# Lightpack_6_0_man.net
KiCad netlist of a schematic drawn in EAGLE
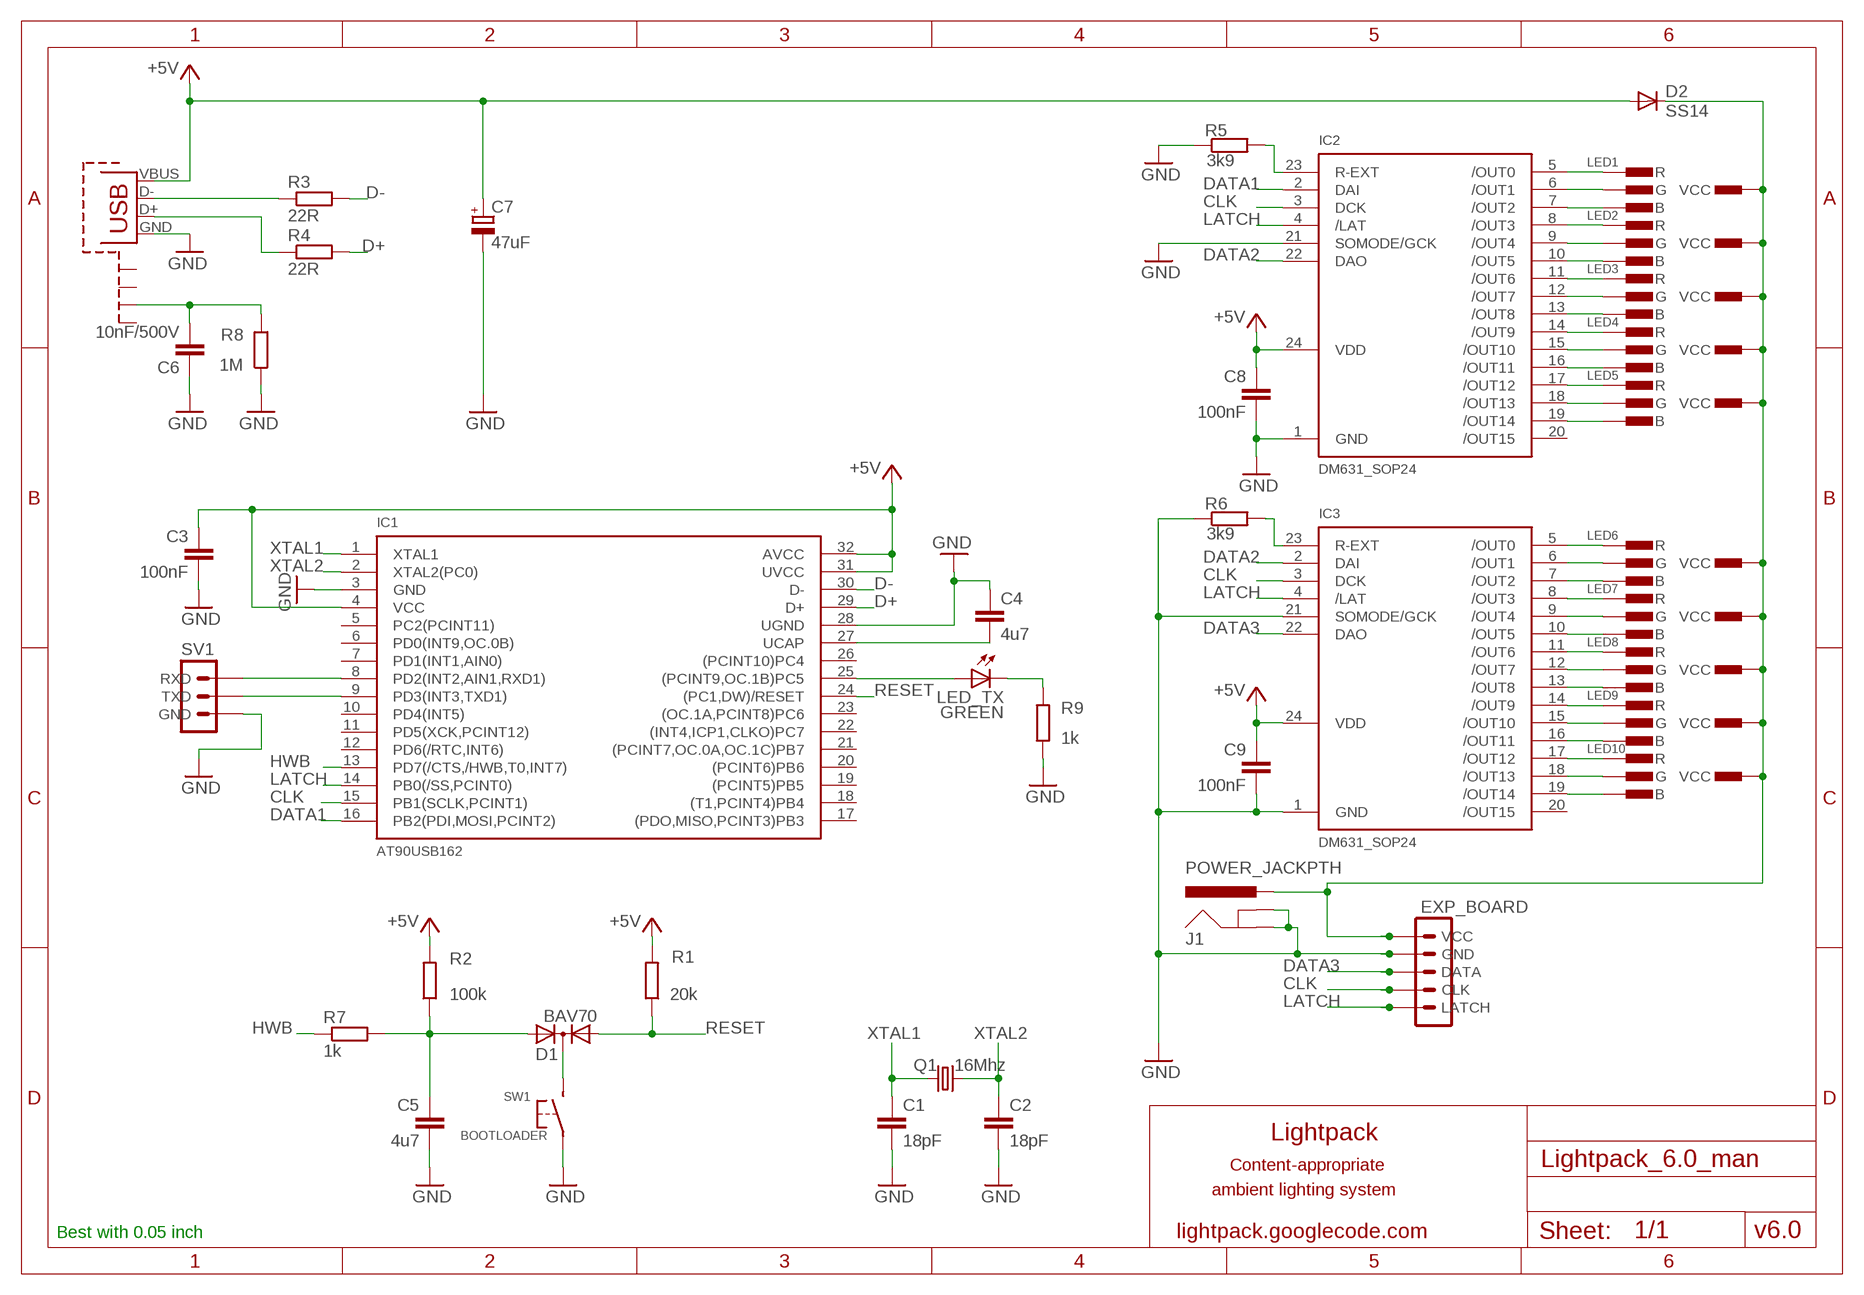
[diagram p0: schematic, sheet 1]

(export (version "E")
  (design (tool "Eeschema 10.0.6"))
  (components
    (comp (ref "C1")
      (value "18pF")
      (footprint "eagle-import:C0805")
      (libsource (lib "eagle-import") (part "C-EUC0805"))
    )
    (comp (ref "C2")
      (value "18pF")
      (footprint "eagle-import:C0805")
      (libsource (lib "eagle-import") (part "C-EUC0805"))
    )
    (comp (ref "C3")
      (value "100nF")
      (footprint "eagle-import:C0805")
      (libsource (lib "eagle-import") (part "C-EUC0805"))
    )
    (comp (ref "C4")
      (value "4u7")
      (footprint "eagle-import:C0805")
      (libsource (lib "eagle-import") (part "C-EUC0805"))
    )
    (comp (ref "C5")
      (value "4u7")
      (footprint "eagle-import:C0805")
      (libsource (lib "eagle-import") (part "C-EUC0805"))
    )
    (comp (ref "C6")
      (value "10nF/500V")
      (footprint "eagle-import:C0805")
      (libsource (lib "eagle-import") (part "C-EUC0805"))
    )
    (comp (ref "C7")
      (value "47uF")
      (footprint "eagle-import:SMC_D")
      (libsource (lib "eagle-import") (part "CPOL-EUSMCD"))
    )
    (comp (ref "C8")
      (value "100nF")
      (footprint "eagle-import:C0805")
      (libsource (lib "eagle-import") (part "C-EUC0805"))
    )
    (comp (ref "C9")
      (value "100nF")
      (footprint "eagle-import:C0805")
      (libsource (lib "eagle-import") (part "C-EUC0805"))
    )
    (comp (ref "D1")
      (value "BAV70")
      (footprint "eagle-import:SOT23")
      (libsource (lib "eagle-import") (part "DIODE-2AC|CASOT23"))
    )
    (comp (ref "D2")
      (value "SS14")
      (footprint "eagle-import:SMB")
      (libsource (lib "eagle-import") (part "DIODE-SMB"))
    )
    (comp (ref "EXP_BOARD")
      (value "MA05-1")
      (footprint "eagle-import:MA05-1")
      (libsource (lib "eagle-import") (part "MA05-1"))
    )
    (comp (ref "IC1")
      (value "AT90USB162")
      (footprint "eagle-import:TQFP32")
      (libsource (lib "eagle-import") (part "AT90USB162"))
    )
    (comp (ref "IC2")
      (value "DM631_SOP24")
      (footprint "eagle-import:SOP24-300-1.27")
      (libsource (lib "eagle-import") (part "DM631_SOP24"))
    )
    (comp (ref "IC3")
      (value "DM631_SOP24")
      (footprint "eagle-import:SOP24-300-1.27")
      (libsource (lib "eagle-import") (part "DM631_SOP24"))
    )
    (comp (ref "J1")
      (value "POWER_JACKPTH")
      (footprint "eagle-import:POWER_JACK_PTH")
      (libsource (lib "eagle-import") (part "POWER_JACKPTH"))
    )
    (comp (ref "LED1")
      (value "CON-RGB-LED")
      (footprint "eagle-import:CON-RGB-LED-TH")
      (libsource (lib "eagle-import") (part "CON-RGB-LED-TH"))
    )
    (comp (ref "LED2")
      (value "CON-RGB-LED")
      (footprint "eagle-import:CON-RGB-LED-TH")
      (libsource (lib "eagle-import") (part "CON-RGB-LED-TH"))
    )
    (comp (ref "LED3")
      (value "CON-RGB-LED")
      (footprint "eagle-import:CON-RGB-LED-TH")
      (libsource (lib "eagle-import") (part "CON-RGB-LED-TH"))
    )
    (comp (ref "LED4")
      (value "CON-RGB-LED")
      (footprint "eagle-import:CON-RGB-LED-TH")
      (libsource (lib "eagle-import") (part "CON-RGB-LED-TH"))
    )
    (comp (ref "LED5")
      (value "CON-RGB-LED")
      (footprint "eagle-import:CON-RGB-LED-TH")
      (libsource (lib "eagle-import") (part "CON-RGB-LED-TH"))
    )
    (comp (ref "LED6")
      (value "CON-RGB-LED")
      (footprint "eagle-import:CON-RGB-LED-TH")
      (libsource (lib "eagle-import") (part "CON-RGB-LED-TH"))
    )
    (comp (ref "LED7")
      (value "CON-RGB-LED")
      (footprint "eagle-import:CON-RGB-LED-TH")
      (libsource (lib "eagle-import") (part "CON-RGB-LED-TH"))
    )
    (comp (ref "LED8")
      (value "CON-RGB-LED")
      (footprint "eagle-import:CON-RGB-LED-TH")
      (libsource (lib "eagle-import") (part "CON-RGB-LED-TH"))
    )
    (comp (ref "LED9")
      (value "CON-RGB-LED")
      (footprint "eagle-import:CON-RGB-LED-TH")
      (libsource (lib "eagle-import") (part "CON-RGB-LED-TH"))
    )
    (comp (ref "LED10")
      (value "CON-RGB-LED")
      (footprint "eagle-import:CON-RGB-LED-TH")
      (libsource (lib "eagle-import") (part "CON-RGB-LED-TH"))
    )
    (comp (ref "LED_TX")
      (value "GREEN")
      (footprint "eagle-import:CHIPLED_0805")
      (libsource (lib "eagle-import") (part "LEDCHIPLED_0805"))
    )
    (comp (ref "Q1")
      (value "16Mhz")
      (footprint "eagle-import:HC49UP")
      (libsource (lib "eagle-import") (part "CRYSTALHC49UP"))
    )
    (comp (ref "R1")
      (value "20k")
      (footprint "eagle-import:R0805")
      (libsource (lib "eagle-import") (part "R-EU_R0805"))
    )
    (comp (ref "R2")
      (value "100k")
      (footprint "eagle-import:R0805")
      (libsource (lib "eagle-import") (part "R-EU_R0805"))
    )
    (comp (ref "R3")
      (value "22R")
      (footprint "eagle-import:R0805")
      (libsource (lib "eagle-import") (part "R-EU_R0805"))
    )
    (comp (ref "R4")
      (value "22R")
      (footprint "eagle-import:R0805")
      (libsource (lib "eagle-import") (part "R-EU_R0805"))
    )
    (comp (ref "R5")
      (value "3k9")
      (footprint "eagle-import:R0805")
      (libsource (lib "eagle-import") (part "R-EU_R0805"))
    )
    (comp (ref "R6")
      (value "3k9")
      (footprint "eagle-import:R0805")
      (libsource (lib "eagle-import") (part "R-EU_R0805"))
    )
    (comp (ref "R7")
      (value "1k")
      (footprint "eagle-import:R0805")
      (libsource (lib "eagle-import") (part "R-EU_R0805"))
    )
    (comp (ref "R8")
      (value "1M")
      (footprint "eagle-import:R0805")
      (libsource (lib "eagle-import") (part "R-EU_R0805"))
    )
    (comp (ref "R9")
      (value "1k")
      (footprint "eagle-import:R0805")
      (libsource (lib "eagle-import") (part "R-EU_R0805"))
    )
    (comp (ref "SV1")
      (value "UART3")
      (footprint "eagle-import:UART3")
      (libsource (lib "eagle-import") (part "UART3"))
    )
    (comp (ref "SW1")
      (value "BOOTLOADER")
      (footprint "eagle-import:BUTTON-SMD")
      (libsource (lib "eagle-import") (part "BUTTON"))
    )
    (comp (ref "X1")
      (value "USB-MB-S")
      (footprint "eagle-import:USB-MB-S")
      (libsource (lib "eagle-import") (part "USB-MB-S"))
    )
  )
  (nets
    (net (code "1") (name "+5V") (class "Default")
      (node (ref "C3") (pin "1") (pinfunction "1_1") (pintype "passive"))
      (node (ref "C7") (pin "+") (pinfunction "+_+") (pintype "passive"))
      (node (ref "C8") (pin "1") (pinfunction "1_1") (pintype "passive"))
      (node (ref "C9") (pin "1") (pinfunction "1_1") (pintype "passive"))
      (node (ref "D2") (pin "A") (pinfunction "A_A") (pintype "passive"))
      (node (ref "IC1") (pin "31") (pinfunction "UVCC_31") (pintype "bidirectional"))
      (node (ref "IC1") (pin "32") (pinfunction "AVCC_32") (pintype "bidirectional"))
      (node (ref "IC1") (pin "4") (pinfunction "VCC_4") (pintype "bidirectional"))
      (node (ref "IC2") (pin "24") (pinfunction "VDD_24") (pintype "bidirectional"))
      (node (ref "IC3") (pin "24") (pinfunction "VDD_24") (pintype "bidirectional"))
      (node (ref "R1") (pin "2") (pinfunction "2_2") (pintype "passive"))
      (node (ref "R2") (pin "2") (pinfunction "2_2") (pintype "passive"))
      (node (ref "X1") (pin "VBUS") (pinfunction "VBUS_VBUS") (pintype "bidirectional"))
    )
    (net (code "2") (name "/CLK") (class "Default")
      (node (ref "EXP_BOARD") (pin "2") (pinfunction "CLK_2") (pintype "passive"))
      (node (ref "IC1") (pin "15") (pinfunction "PB1(SCLK,PCINT1)_15") (pintype "bidirectional"))
      (node (ref "IC2") (pin "3") (pinfunction "DCK_3") (pintype "bidirectional"))
      (node (ref "IC3") (pin "3") (pinfunction "DCK_3") (pintype "bidirectional"))
    )
    (net (code "3") (name "/D+") (class "Default")
      (node (ref "IC1") (pin "29") (pinfunction "D+_29") (pintype "bidirectional"))
      (node (ref "R4") (pin "2") (pinfunction "2_2") (pintype "passive"))
    )
    (net (code "4") (name "/D-") (class "Default")
      (node (ref "IC1") (pin "30") (pinfunction "D-_30") (pintype "bidirectional"))
      (node (ref "R3") (pin "2") (pinfunction "2_2") (pintype "passive"))
    )
    (net (code "5") (name "/DATA1") (class "Default")
      (node (ref "IC1") (pin "16") (pinfunction "PB2(PDI,MOSI,PCINT2)_16") (pintype "bidirectional"))
      (node (ref "IC2") (pin "2") (pinfunction "DAI_2") (pintype "bidirectional"))
    )
    (net (code "6") (name "/DATA2") (class "Default")
      (node (ref "IC2") (pin "22") (pinfunction "DAO_22") (pintype "bidirectional"))
      (node (ref "IC3") (pin "2") (pinfunction "DAI_2") (pintype "bidirectional"))
    )
    (net (code "7") (name "/DATA3") (class "Default")
      (node (ref "EXP_BOARD") (pin "3") (pinfunction "DATA_3") (pintype "passive"))
      (node (ref "IC3") (pin "22") (pinfunction "DAO_22") (pintype "bidirectional"))
    )
    (net (code "8") (name "/HWB") (class "Default")
      (node (ref "IC1") (pin "13") (pinfunction "PD7(/CTS,/HWB,T0,INT7)_13") (pintype "bidirectional"))
      (node (ref "R7") (pin "1") (pinfunction "1_1") (pintype "passive"))
    )
    (net (code "9") (name "/LATCH") (class "Default")
      (node (ref "EXP_BOARD") (pin "1") (pinfunction "LATCH_1") (pintype "passive"))
      (node (ref "IC1") (pin "14") (pinfunction "PB0(/SS,PCINT0)_14") (pintype "bidirectional"))
      (node (ref "IC2") (pin "4") (pinfunction "/LAT_4") (pintype "bidirectional"))
      (node (ref "IC3") (pin "4") (pinfunction "/LAT_4") (pintype "bidirectional"))
    )
    (net (code "10") (name "/RESET") (class "Default")
      (node (ref "D1") (pin "1") (pinfunction "A1_1") (pintype "passive"))
      (node (ref "IC1") (pin "24") (pinfunction "(PC1,DW)/RESET_24") (pintype "bidirectional"))
      (node (ref "R1") (pin "1") (pinfunction "1_1") (pintype "passive"))
    )
    (net (code "11") (name "/XTAL1") (class "Default")
      (node (ref "C1") (pin "1") (pinfunction "1_1") (pintype "passive"))
      (node (ref "IC1") (pin "1") (pinfunction "XTAL1_1") (pintype "bidirectional"))
      (node (ref "Q1") (pin "1") (pinfunction "1_1") (pintype "passive"))
    )
    (net (code "12") (name "/XTAL2") (class "Default")
      (node (ref "C2") (pin "1") (pinfunction "1_1") (pintype "passive"))
      (node (ref "IC1") (pin "2") (pinfunction "XTAL2(PC0)_2") (pintype "bidirectional"))
      (node (ref "Q1") (pin "2") (pinfunction "2_2") (pintype "passive"))
    )
    (net (code "13") (name "GND") (class "Default")
      (node (ref "C1") (pin "2") (pinfunction "2_2") (pintype "passive"))
      (node (ref "C2") (pin "2") (pinfunction "2_2") (pintype "passive"))
      (node (ref "C3") (pin "2") (pinfunction "2_2") (pintype "passive"))
      (node (ref "C4") (pin "1") (pinfunction "1_1") (pintype "passive"))
      (node (ref "C5") (pin "2") (pinfunction "2_2") (pintype "passive"))
      (node (ref "C6") (pin "1") (pinfunction "1_1") (pintype "passive"))
      (node (ref "C7") (pin "-") (pinfunction "-_-") (pintype "passive"))
      (node (ref "C8") (pin "2") (pinfunction "2_2") (pintype "passive"))
      (node (ref "C9") (pin "2") (pinfunction "2_2") (pintype "passive"))
      (node (ref "EXP_BOARD") (pin "4") (pinfunction "GND_4") (pintype "passive"))
      (node (ref "IC1") (pin "28") (pinfunction "UGND_28") (pintype "bidirectional"))
      (node (ref "IC1") (pin "3") (pinfunction "GND_3") (pintype "bidirectional"))
      (node (ref "IC2") (pin "1") (pinfunction "GND_1") (pintype "bidirectional"))
      (node (ref "IC2") (pin "21") (pinfunction "SOMODE/GCK_21") (pintype "bidirectional"))
      (node (ref "IC3") (pin "1") (pinfunction "GND_1") (pintype "bidirectional"))
      (node (ref "IC3") (pin "21") (pinfunction "SOMODE/GCK_21") (pintype "bidirectional"))
      (node (ref "J1") (pin "GND") (pinfunction "GND_GND") (pintype "bidirectional"))
      (node (ref "J1") (pin "GNDBREAK") (pinfunction "GNDBREAK_GNDBREAK") (pintype "bidirectional"))
      (node (ref "R5") (pin "1") (pinfunction "1_1") (pintype "passive"))
      (node (ref "R6") (pin "1") (pinfunction "1_1") (pintype "passive"))
      (node (ref "R8") (pin "1") (pinfunction "1_1") (pintype "passive"))
      (node (ref "R9") (pin "1") (pinfunction "1_1") (pintype "passive"))
      (node (ref "SV1") (pin "1-L") (pinfunction "GND_1-L") (pintype "passive"))
      (node (ref "SW1") (pin "1") (pinfunction "1_1") (pintype "passive"))
      (node (ref "X1") (pin "GND") (pinfunction "GND_GND") (pintype "bidirectional"))
    )
    (net (code "14") (name "Net-(C6-Pad2)") (class "Default")
      (node (ref "C6") (pin "2") (pinfunction "2_2") (pintype "passive"))
      (node (ref "R8") (pin "2") (pinfunction "2_2") (pintype "passive"))
      (node (ref "X1") (pin "SHIELD3") (pinfunction "SHIELD3_SHIELD3") (pintype "bidirectional"))
    )
    (net (code "15") (name "Net-(D1-A2)") (class "Default")
      (node (ref "C5") (pin "1") (pinfunction "1_1") (pintype "passive"))
      (node (ref "D1") (pin "2") (pinfunction "A2_2") (pintype "passive"))
      (node (ref "R2") (pin "1") (pinfunction "1_1") (pintype "passive"))
      (node (ref "R7") (pin "2") (pinfunction "2_2") (pintype "passive"))
    )
    (net (code "16") (name "Net-(D1-C)") (class "Default")
      (node (ref "D1") (pin "3") (pinfunction "C_3") (pintype "passive"))
      (node (ref "SW1") (pin "2") (pinfunction "2_2") (pintype "passive"))
    )
    (net (code "17") (name "Net-(EXP_BOARD-VCC)") (class "Default")
      (node (ref "D2") (pin "C") (pinfunction "C_C") (pintype "passive"))
      (node (ref "EXP_BOARD") (pin "5") (pinfunction "VCC_5") (pintype "passive"))
      (node (ref "J1") (pin "PWR") (pinfunction "PWR_PWR") (pintype "bidirectional"))
      (node (ref "LED1") (pin "4.VCC") (pinfunction "VCC_4.VCC") (pintype "bidirectional"))
      (node (ref "LED10") (pin "4.VCC") (pinfunction "VCC_4.VCC") (pintype "bidirectional"))
      (node (ref "LED2") (pin "4.VCC") (pinfunction "VCC_4.VCC") (pintype "bidirectional"))
      (node (ref "LED3") (pin "4.VCC") (pinfunction "VCC_4.VCC") (pintype "bidirectional"))
      (node (ref "LED4") (pin "4.VCC") (pinfunction "VCC_4.VCC") (pintype "bidirectional"))
      (node (ref "LED5") (pin "4.VCC") (pinfunction "VCC_4.VCC") (pintype "bidirectional"))
      (node (ref "LED6") (pin "4.VCC") (pinfunction "VCC_4.VCC") (pintype "bidirectional"))
      (node (ref "LED7") (pin "4.VCC") (pinfunction "VCC_4.VCC") (pintype "bidirectional"))
      (node (ref "LED8") (pin "4.VCC") (pinfunction "VCC_4.VCC") (pintype "bidirectional"))
      (node (ref "LED9") (pin "4.VCC") (pinfunction "VCC_4.VCC") (pintype "bidirectional"))
    )
    (net (code "18") (name "Net-(IC1-(PCINT9,OC.1B)PC5)") (class "Default")
      (node (ref "IC1") (pin "25") (pinfunction "(PCINT9,OC.1B)PC5_25") (pintype "bidirectional"))
      (node (ref "LED_TX") (pin "A") (pinfunction "A_A") (pintype "passive"))
    )
    (net (code "19") (name "Net-(IC1-PD2(INT2,AIN1,RXD1))") (class "Default")
      (node (ref "IC1") (pin "8") (pinfunction "PD2(INT2,AIN1,RXD1)_8") (pintype "bidirectional"))
      (node (ref "SV1") (pin "2") (pinfunction "RXD_2") (pintype "passive"))
    )
    (net (code "20") (name "Net-(IC1-PD3(INT3,TXD1))") (class "Default")
      (node (ref "IC1") (pin "9") (pinfunction "PD3(INT3,TXD1)_9") (pintype "bidirectional"))
      (node (ref "SV1") (pin "3-R") (pinfunction "TXD_3-R") (pintype "passive"))
    )
    (net (code "21") (name "Net-(IC1-UCAP)") (class "Default")
      (node (ref "C4") (pin "2") (pinfunction "2_2") (pintype "passive"))
      (node (ref "IC1") (pin "27") (pinfunction "UCAP_27") (pintype "bidirectional"))
    )
    (net (code "22") (name "Net-(IC2-R-EXT)") (class "Default")
      (node (ref "IC2") (pin "23") (pinfunction "R-EXT_23") (pintype "bidirectional"))
      (node (ref "R5") (pin "2") (pinfunction "2_2") (pintype "passive"))
    )
    (net (code "23") (name "Net-(IC2-{slash}OUT0)") (class "Default")
      (node (ref "IC2") (pin "5") (pinfunction "/OUT0_5") (pintype "bidirectional"))
      (node (ref "LED1") (pin "3.R") (pinfunction "R_3.R") (pintype "bidirectional"))
    )
    (net (code "24") (name "Net-(IC2-{slash}OUT1)") (class "Default")
      (node (ref "IC2") (pin "6") (pinfunction "/OUT1_6") (pintype "bidirectional"))
      (node (ref "LED1") (pin "2.G") (pinfunction "G_2.G") (pintype "bidirectional"))
    )
    (net (code "25") (name "Net-(IC2-{slash}OUT2)") (class "Default")
      (node (ref "IC2") (pin "7") (pinfunction "/OUT2_7") (pintype "bidirectional"))
      (node (ref "LED1") (pin "1.B") (pinfunction "B_1.B") (pintype "bidirectional"))
    )
    (net (code "26") (name "Net-(IC2-{slash}OUT3)") (class "Default")
      (node (ref "IC2") (pin "8") (pinfunction "/OUT3_8") (pintype "bidirectional"))
      (node (ref "LED2") (pin "3.R") (pinfunction "R_3.R") (pintype "bidirectional"))
    )
    (net (code "27") (name "Net-(IC2-{slash}OUT4)") (class "Default")
      (node (ref "IC2") (pin "9") (pinfunction "/OUT4_9") (pintype "bidirectional"))
      (node (ref "LED2") (pin "2.G") (pinfunction "G_2.G") (pintype "bidirectional"))
    )
    (net (code "28") (name "Net-(IC2-{slash}OUT5)") (class "Default")
      (node (ref "IC2") (pin "10") (pinfunction "/OUT5_10") (pintype "bidirectional"))
      (node (ref "LED2") (pin "1.B") (pinfunction "B_1.B") (pintype "bidirectional"))
    )
    (net (code "29") (name "Net-(IC2-{slash}OUT6)") (class "Default")
      (node (ref "IC2") (pin "11") (pinfunction "/OUT6_11") (pintype "bidirectional"))
      (node (ref "LED3") (pin "3.R") (pinfunction "R_3.R") (pintype "bidirectional"))
    )
    (net (code "30") (name "Net-(IC2-{slash}OUT7)") (class "Default")
      (node (ref "IC2") (pin "12") (pinfunction "/OUT7_12") (pintype "bidirectional"))
      (node (ref "LED3") (pin "2.G") (pinfunction "G_2.G") (pintype "bidirectional"))
    )
    (net (code "31") (name "Net-(IC2-{slash}OUT8)") (class "Default")
      (node (ref "IC2") (pin "13") (pinfunction "/OUT8_13") (pintype "bidirectional"))
      (node (ref "LED3") (pin "1.B") (pinfunction "B_1.B") (pintype "bidirectional"))
    )
    (net (code "32") (name "Net-(IC2-{slash}OUT9)") (class "Default")
      (node (ref "IC2") (pin "14") (pinfunction "/OUT9_14") (pintype "bidirectional"))
      (node (ref "LED4") (pin "3.R") (pinfunction "R_3.R") (pintype "bidirectional"))
    )
    (net (code "33") (name "Net-(IC2-{slash}OUT10)") (class "Default")
      (node (ref "IC2") (pin "15") (pinfunction "/OUT10_15") (pintype "bidirectional"))
      (node (ref "LED4") (pin "2.G") (pinfunction "G_2.G") (pintype "bidirectional"))
    )
    (net (code "34") (name "Net-(IC2-{slash}OUT11)") (class "Default")
      (node (ref "IC2") (pin "16") (pinfunction "/OUT11_16") (pintype "bidirectional"))
      (node (ref "LED4") (pin "1.B") (pinfunction "B_1.B") (pintype "bidirectional"))
    )
    (net (code "35") (name "Net-(IC2-{slash}OUT12)") (class "Default")
      (node (ref "IC2") (pin "17") (pinfunction "/OUT12_17") (pintype "bidirectional"))
      (node (ref "LED5") (pin "3.R") (pinfunction "R_3.R") (pintype "bidirectional"))
    )
    (net (code "36") (name "Net-(IC2-{slash}OUT13)") (class "Default")
      (node (ref "IC2") (pin "18") (pinfunction "/OUT13_18") (pintype "bidirectional"))
      (node (ref "LED5") (pin "2.G") (pinfunction "G_2.G") (pintype "bidirectional"))
    )
    (net (code "37") (name "Net-(IC2-{slash}OUT14)") (class "Default")
      (node (ref "IC2") (pin "19") (pinfunction "/OUT14_19") (pintype "bidirectional"))
      (node (ref "LED5") (pin "1.B") (pinfunction "B_1.B") (pintype "bidirectional"))
    )
    (net (code "38") (name "Net-(IC3-R-EXT)") (class "Default")
      (node (ref "IC3") (pin "23") (pinfunction "R-EXT_23") (pintype "bidirectional"))
      (node (ref "R6") (pin "2") (pinfunction "2_2") (pintype "passive"))
    )
    (net (code "39") (name "Net-(IC3-{slash}OUT0)") (class "Default")
      (node (ref "IC3") (pin "5") (pinfunction "/OUT0_5") (pintype "bidirectional"))
      (node (ref "LED6") (pin "3.R") (pinfunction "R_3.R") (pintype "bidirectional"))
    )
    (net (code "40") (name "Net-(IC3-{slash}OUT1)") (class "Default")
      (node (ref "IC3") (pin "6") (pinfunction "/OUT1_6") (pintype "bidirectional"))
      (node (ref "LED6") (pin "2.G") (pinfunction "G_2.G") (pintype "bidirectional"))
    )
    (net (code "41") (name "Net-(IC3-{slash}OUT2)") (class "Default")
      (node (ref "IC3") (pin "7") (pinfunction "/OUT2_7") (pintype "bidirectional"))
      (node (ref "LED6") (pin "1.B") (pinfunction "B_1.B") (pintype "bidirectional"))
    )
    (net (code "42") (name "Net-(IC3-{slash}OUT3)") (class "Default")
      (node (ref "IC3") (pin "8") (pinfunction "/OUT3_8") (pintype "bidirectional"))
      (node (ref "LED7") (pin "3.R") (pinfunction "R_3.R") (pintype "bidirectional"))
    )
    (net (code "43") (name "Net-(IC3-{slash}OUT4)") (class "Default")
      (node (ref "IC3") (pin "9") (pinfunction "/OUT4_9") (pintype "bidirectional"))
      (node (ref "LED7") (pin "2.G") (pinfunction "G_2.G") (pintype "bidirectional"))
    )
    (net (code "44") (name "Net-(IC3-{slash}OUT5)") (class "Default")
      (node (ref "IC3") (pin "10") (pinfunction "/OUT5_10") (pintype "bidirectional"))
      (node (ref "LED7") (pin "1.B") (pinfunction "B_1.B") (pintype "bidirectional"))
    )
    (net (code "45") (name "Net-(IC3-{slash}OUT6)") (class "Default")
      (node (ref "IC3") (pin "11") (pinfunction "/OUT6_11") (pintype "bidirectional"))
      (node (ref "LED8") (pin "3.R") (pinfunction "R_3.R") (pintype "bidirectional"))
    )
    (net (code "46") (name "Net-(IC3-{slash}OUT7)") (class "Default")
      (node (ref "IC3") (pin "12") (pinfunction "/OUT7_12") (pintype "bidirectional"))
      (node (ref "LED8") (pin "2.G") (pinfunction "G_2.G") (pintype "bidirectional"))
    )
    (net (code "47") (name "Net-(IC3-{slash}OUT8)") (class "Default")
      (node (ref "IC3") (pin "13") (pinfunction "/OUT8_13") (pintype "bidirectional"))
      (node (ref "LED8") (pin "1.B") (pinfunction "B_1.B") (pintype "bidirectional"))
    )
    (net (code "48") (name "Net-(IC3-{slash}OUT9)") (class "Default")
      (node (ref "IC3") (pin "14") (pinfunction "/OUT9_14") (pintype "bidirectional"))
      (node (ref "LED9") (pin "3.R") (pinfunction "R_3.R") (pintype "bidirectional"))
    )
    (net (code "49") (name "Net-(IC3-{slash}OUT10)") (class "Default")
      (node (ref "IC3") (pin "15") (pinfunction "/OUT10_15") (pintype "bidirectional"))
      (node (ref "LED9") (pin "2.G") (pinfunction "G_2.G") (pintype "bidirectional"))
    )
    (net (code "50") (name "Net-(IC3-{slash}OUT11)") (class "Default")
      (node (ref "IC3") (pin "16") (pinfunction "/OUT11_16") (pintype "bidirectional"))
      (node (ref "LED9") (pin "1.B") (pinfunction "B_1.B") (pintype "bidirectional"))
    )
    (net (code "51") (name "Net-(IC3-{slash}OUT12)") (class "Default")
      (node (ref "IC3") (pin "17") (pinfunction "/OUT12_17") (pintype "bidirectional"))
      (node (ref "LED10") (pin "3.R") (pinfunction "R_3.R") (pintype "bidirectional"))
    )
    (net (code "52") (name "Net-(IC3-{slash}OUT13)") (class "Default")
      (node (ref "IC3") (pin "18") (pinfunction "/OUT13_18") (pintype "bidirectional"))
      (node (ref "LED10") (pin "2.G") (pinfunction "G_2.G") (pintype "bidirectional"))
    )
    (net (code "53") (name "Net-(IC3-{slash}OUT14)") (class "Default")
      (node (ref "IC3") (pin "19") (pinfunction "/OUT14_19") (pintype "bidirectional"))
      (node (ref "LED10") (pin "1.B") (pinfunction "B_1.B") (pintype "bidirectional"))
    )
    (net (code "54") (name "Net-(LED_TX-PadC)") (class "Default")
      (node (ref "LED_TX") (pin "C") (pinfunction "C_C") (pintype "passive"))
      (node (ref "R9") (pin "2") (pinfunction "2_2") (pintype "passive"))
    )
    (net (code "55") (name "Net-(R3-Pad1)") (class "Default")
      (node (ref "R3") (pin "1") (pinfunction "1_1") (pintype "passive"))
      (node (ref "X1") (pin "D-") (pinfunction "D-_D-") (pintype "bidirectional"))
    )
    (net (code "56") (name "Net-(R4-Pad1)") (class "Default")
      (node (ref "R4") (pin "1") (pinfunction "1_1") (pintype "passive"))
      (node (ref "X1") (pin "D+") (pinfunction "D+_D+") (pintype "bidirectional"))
    )
    (net (code "57") (name "unconnected-(IC1-(INT4,ICP1,CLKO)PC7-Pad22)") (class "Default")
      (node (ref "IC1") (pin "22") (pinfunction "(INT4,ICP1,CLKO)PC7_22") (pintype "bidirectional"))
    )
    (net (code "58") (name "unconnected-(IC1-(OC.1A,PCINT8)PC6-Pad23)") (class "Default")
      (node (ref "IC1") (pin "23") (pinfunction "(OC.1A,PCINT8)PC6_23") (pintype "bidirectional"))
    )
    (net (code "59") (name "unconnected-(IC1-(PCINT5)PB5-Pad19)") (class "Default")
      (node (ref "IC1") (pin "19") (pinfunction "(PCINT5)PB5_19") (pintype "bidirectional"))
    )
    (net (code "60") (name "unconnected-(IC1-(PCINT6)PB6-Pad20)") (class "Default")
      (node (ref "IC1") (pin "20") (pinfunction "(PCINT6)PB6_20") (pintype "bidirectional"))
    )
    (net (code "61") (name "unconnected-(IC1-(PCINT7,OC.0A,OC.1C)PB7-Pad21)") (class "Default")
      (node (ref "IC1") (pin "21") (pinfunction "(PCINT7,OC.0A,OC.1C)PB7_21") (pintype "bidirectional"))
    )
    (net (code "62") (name "unconnected-(IC1-(PCINT10)PC4-Pad26)") (class "Default")
      (node (ref "IC1") (pin "26") (pinfunction "(PCINT10)PC4_26") (pintype "bidirectional"))
    )
    (net (code "63") (name "unconnected-(IC1-(PDO,MISO,PCINT3)PB3-Pad17)") (class "Default")
      (node (ref "IC1") (pin "17") (pinfunction "(PDO,MISO,PCINT3)PB3_17") (pintype "bidirectional"))
    )
    (net (code "64") (name "unconnected-(IC1-(T1,PCINT4)PB4-Pad18)") (class "Default")
      (node (ref "IC1") (pin "18") (pinfunction "(T1,PCINT4)PB4_18") (pintype "bidirectional"))
    )
    (net (code "65") (name "unconnected-(IC1-PC2(PCINT11)-Pad5)") (class "Default")
      (node (ref "IC1") (pin "5") (pinfunction "PC2(PCINT11)_5") (pintype "bidirectional"))
    )
    (net (code "66") (name "unconnected-(IC1-PD0(INT9,OC.0B)-Pad6)") (class "Default")
      (node (ref "IC1") (pin "6") (pinfunction "PD0(INT9,OC.0B)_6") (pintype "bidirectional"))
    )
    (net (code "67") (name "unconnected-(IC1-PD1(INT1,AIN0)-Pad7)") (class "Default")
      (node (ref "IC1") (pin "7") (pinfunction "PD1(INT1,AIN0)_7") (pintype "bidirectional"))
    )
    (net (code "68") (name "unconnected-(IC1-PD4(INT5)-Pad10)") (class "Default")
      (node (ref "IC1") (pin "10") (pinfunction "PD4(INT5)_10") (pintype "bidirectional"))
    )
    (net (code "69") (name "unconnected-(IC1-PD5(XCK,PCINT12)-Pad11)") (class "Default")
      (node (ref "IC1") (pin "11") (pinfunction "PD5(XCK,PCINT12)_11") (pintype "bidirectional"))
    )
    (net (code "70") (name "unconnected-(IC1-PD6({slash}RTC,INT6)-Pad12)") (class "Default")
      (node (ref "IC1") (pin "12") (pinfunction "PD6(/RTC,INT6)_12") (pintype "bidirectional"))
    )
    (net (code "71") (name "unconnected-(IC2-{slash}OUT15-Pad20)") (class "Default")
      (node (ref "IC2") (pin "20") (pinfunction "/OUT15_20") (pintype "bidirectional"))
    )
    (net (code "72") (name "unconnected-(IC3-{slash}OUT15-Pad20)") (class "Default")
      (node (ref "IC3") (pin "20") (pinfunction "/OUT15_20") (pintype "bidirectional"))
    )
    (net (code "73") (name "unconnected-(X1-PadSHIELD1)") (class "Default")
      (node (ref "X1") (pin "SHIELD1") (pinfunction "SHIELD1_SHIELD1") (pintype "bidirectional"))
    )
    (net (code "74") (name "unconnected-(X1-PadSHIELD2)") (class "Default")
      (node (ref "X1") (pin "SHIELD2") (pinfunction "SHIELD2_SHIELD2") (pintype "bidirectional"))
    )
    (net (code "75") (name "unconnected-(X1-PadSHIELD4)") (class "Default")
      (node (ref "X1") (pin "SHIELD4") (pinfunction "SHIELD4_SHIELD4") (pintype "bidirectional"))
    )
  )
)
